# POWER.net
KiCad netlist of a schematic drawn in Altium Designer
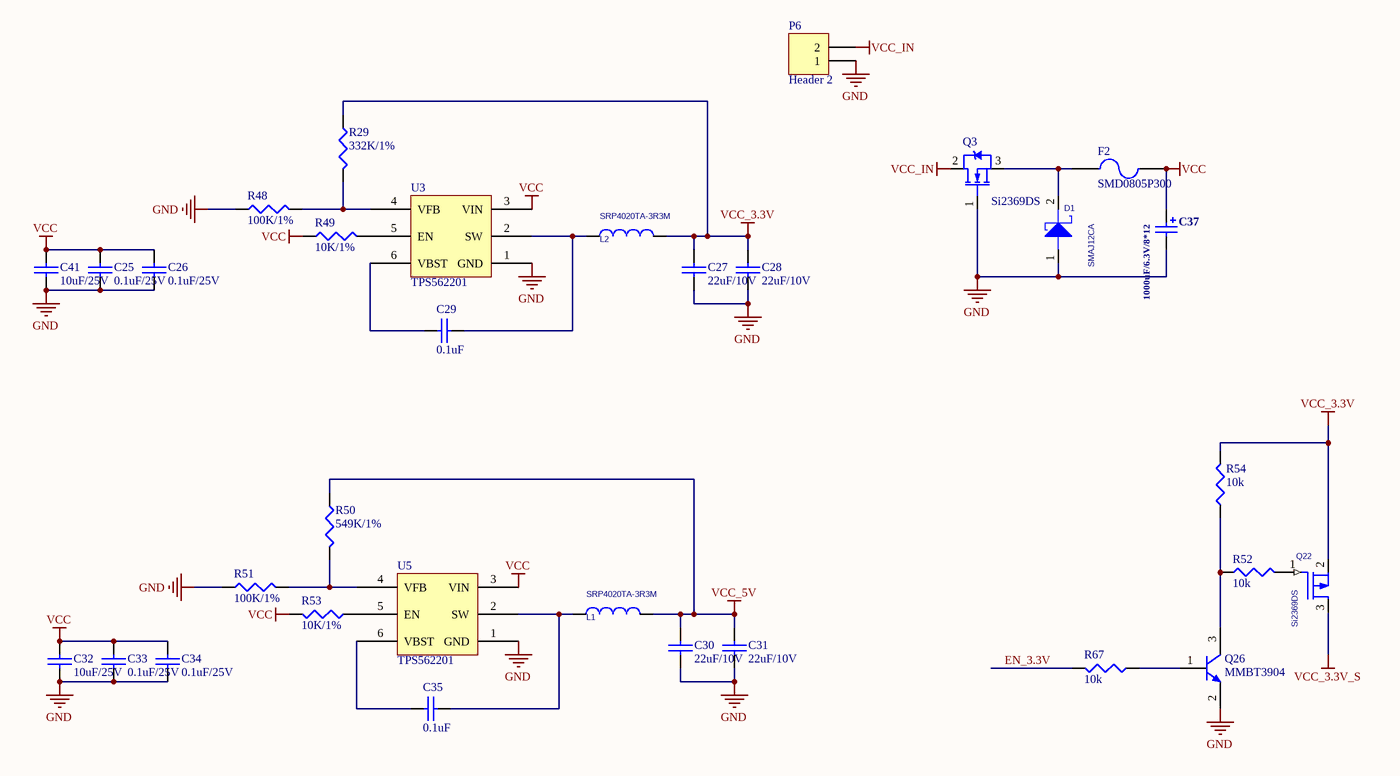
[diagram p0: POWER.SchDoc]

(export (version "E")
  (design (tool "Eeschema 10.0.6"))
  (components
    (comp (ref "C25")
      (value "0.1uF/25V")
      (footprint "0603C")
      (description "Capacitor")
      (libsource (lib "ZWLIntegrated_Library") (part "CAP"))
    )
    (comp (ref "C26")
      (value "0.1uF/25V")
      (footprint "0603C")
      (description "Capacitor")
      (libsource (lib "ZWLIntegrated_Library") (part "CAP"))
    )
    (comp (ref "C27")
      (value "22uF/10V")
      (footprint "1206C")
      (description "Capacitor")
      (libsource (lib "ZWLIntegrated_Library") (part "CAP"))
    )
    (comp (ref "C28")
      (value "22uF/10V")
      (footprint "1206C")
      (description "Capacitor")
      (libsource (lib "ZWLIntegrated_Library") (part "CAP"))
    )
    (comp (ref "C29")
      (value "0.1uF")
      (footprint "0603C")
      (description "Capacitor")
      (libsource (lib "ZWLIntegrated_Library") (part "CAP"))
    )
    (comp (ref "C30")
      (value "22uF/10V")
      (footprint "1206C")
      (description "Capacitor")
      (libsource (lib "ZWLIntegrated_Library") (part "CAP"))
    )
    (comp (ref "C31")
      (value "22uF/10V")
      (footprint "1206C")
      (description "Capacitor")
      (libsource (lib "ZWLIntegrated_Library") (part "CAP"))
    )
    (comp (ref "C32")
      (value "10uF/25V")
      (footprint "0603C")
      (description "Capacitor")
      (libsource (lib "ZWLIntegrated_Library") (part "CAP"))
    )
    (comp (ref "C33")
      (value "0.1uF/25V")
      (footprint "0603C")
      (description "Capacitor")
      (libsource (lib "ZWLIntegrated_Library") (part "CAP"))
    )
    (comp (ref "C34")
      (value "0.1uF/25V")
      (footprint "0603C")
      (description "Capacitor")
      (libsource (lib "ZWLIntegrated_Library") (part "CAP"))
    )
    (comp (ref "C35")
      (value "0.1uF")
      (footprint "0603C")
      (description "Capacitor")
      (libsource (lib "ZWLIntegrated_Library") (part "CAP"))
    )
    (comp (ref "C37")
      (value "1000uF/6.3V/8*12")
      (footprint "8*12")
      (description "Polarized Capacitor (Surface Mount)")
      (libsource (lib "KT_iBeacon") (part "Cap Pol3"))
    )
    (comp (ref "C41")
      (value "10uF/25V")
      (footprint "0603C")
      (description "Capacitor")
      (libsource (lib "ZWLIntegrated_Library") (part "CAP"))
    )
    (comp (ref "D1")
      (value "SMAJ12CA")
      (footprint "SMA")
      (libsource (lib "KT_iBeacon") (part "DIODE_SCHOTTKY_0"))
    )
    (comp (ref "F2")
      (value "SMD0805P300")
      (footprint "0805R")
      (description "Fuse")
      (fields (field (name "PUBLISHER") "Altium Limited"))
      (libsource (lib "Miscellaneous Devices") (part "Fuse 2"))
    )
    (comp (ref "L1") (value "SRP4020TA-3R3M") (footprint "CD_4*4") (libsource (lib "*") (part "INDUCTOR_1")))
    (comp (ref "L2") (value "SRP4020TA-3R3M") (footprint "CD_4*4") (libsource (lib "*") (part "INDUCTOR_1")))
    (comp (ref "P6")
      (value "Header 2")
      (footprint "2X2.54MMZ")
      (description "Header, 2-Pin")
      (fields (field (name "PUBLISHER") "Altium Limited"))
      (libsource (lib "Miscellaneous Connectors") (part "Header 2"))
    )
    (comp (ref "Q3")
      (value "Si2369DS")
      (footprint "sot23-3")
      (description "NMOSFET")
      (libsource (lib "SM") (part "NCE4060K"))
    )
    (comp (ref "Q22") (value "Si2369DS") (footprint "SOT23") (libsource (lib "*") (part "MOSFET P_1")))
    (comp (ref "Q26") (value "MMBT3904") (footprint "SOT23-3") (libsource (lib "Schlib1") (part "NPN")))
    (comp (ref "R29")
      (value "332K/1%")
      (footprint "0603R")
      (libsource (lib "ZWLIntegrated_Library") (part "RES1"))
    )
    (comp (ref "R48")
      (value "100K/1%")
      (footprint "0603R")
      (libsource (lib "ZWLIntegrated_Library") (part "RES1"))
    )
    (comp (ref "R49")
      (value "10K/1%")
      (footprint "0603R")
      (libsource (lib "ZWLIntegrated_Library") (part "RES1"))
    )
    (comp (ref "R50")
      (value "549K/1%")
      (footprint "0603R")
      (libsource (lib "ZWLIntegrated_Library") (part "RES1"))
    )
    (comp (ref "R51")
      (value "100K/1%")
      (footprint "0603R")
      (libsource (lib "ZWLIntegrated_Library") (part "RES1"))
    )
    (comp (ref "R52")
      (value "10k")
      (footprint "0603R")
      (libsource (lib "ZWLIntegrated_Library") (part "RES1"))
    )
    (comp (ref "R53")
      (value "10K/1%")
      (footprint "0603R")
      (libsource (lib "ZWLIntegrated_Library") (part "RES1"))
    )
    (comp (ref "R54")
      (value "10k")
      (footprint "0603R")
      (libsource (lib "ZWLIntegrated_Library") (part "RES1"))
    )
    (comp (ref "R67")
      (value "10k")
      (footprint "0603R")
      (libsource (lib "ZWLIntegrated_Library") (part "RES1"))
    )
    (comp (ref "U3")
      (value "TPS562201")
      (footprint "SOT-23-6")
      (libsource (lib "Schlib_20110825") (part "TPS562201"))
    )
    (comp (ref "U5")
      (value "TPS562201")
      (footprint "SOT-23-6")
      (libsource (lib "Schlib_20110825") (part "TPS562201"))
    )
  )
  (nets
    (net (code "1") (name "/EN_3.3V") (class "Default")
      (node (ref "R67") (pin "2") (pinfunction "2_2") (pintype "passive"))
    )
    (net (code "2") (name "GND") (class "Default")
      (node (ref "C25") (pin "1") (pinfunction "1_1") (pintype "passive"))
      (node (ref "C26") (pin "1") (pinfunction "1_1") (pintype "passive"))
      (node (ref "C27") (pin "2") (pinfunction "2_2") (pintype "passive"))
      (node (ref "C28") (pin "2") (pinfunction "2_2") (pintype "passive"))
      (node (ref "C30") (pin "2") (pinfunction "2_2") (pintype "passive"))
      (node (ref "C31") (pin "2") (pinfunction "2_2") (pintype "passive"))
      (node (ref "C32") (pin "1") (pinfunction "1_1") (pintype "passive"))
      (node (ref "C33") (pin "1") (pinfunction "1_1") (pintype "passive"))
      (node (ref "C34") (pin "1") (pinfunction "1_1") (pintype "passive"))
      (node (ref "C37") (pin "2") (pinfunction "2_2") (pintype "passive"))
      (node (ref "C41") (pin "1") (pinfunction "1_1") (pintype "passive"))
      (node (ref "D1") (pin "1") (pinfunction "1_1") (pintype "passive"))
      (node (ref "P6") (pin "1") (pinfunction "1_1") (pintype "passive"))
      (node (ref "Q26") (pin "2") (pinfunction "E_2") (pintype "passive"))
      (node (ref "Q3") (pin "1") (pinfunction "G_1") (pintype "passive"))
      (node (ref "R48") (pin "1") (pinfunction "1_1") (pintype "passive"))
      (node (ref "R51") (pin "1") (pinfunction "1_1") (pintype "passive"))
      (node (ref "U3") (pin "1") (pinfunction "GND_1") (pintype "passive"))
      (node (ref "U5") (pin "1") (pinfunction "GND_1") (pintype "passive"))
    )
    (net (code "3") (name "Net-(Q3-S)") (class "Default")
      (node (ref "D1") (pin "2") (pinfunction "2_2") (pintype "passive"))
      (node (ref "F2") (pin "1") (pinfunction "1_1") (pintype "passive"))
      (node (ref "Q3") (pin "3") (pinfunction "S_3") (pintype "passive"))
    )
    (net (code "4") (name "Net-(Q22-GATE)") (class "Default")
      (node (ref "Q22") (pin "1") (pinfunction "GATE_1") (pintype "input"))
      (node (ref "R52") (pin "2") (pinfunction "2_2") (pintype "passive"))
    )
    (net (code "5") (name "Net-(Q26-B)") (class "Default")
      (node (ref "Q26") (pin "1") (pinfunction "B_1") (pintype "passive"))
      (node (ref "R67") (pin "1") (pinfunction "1_1") (pintype "passive"))
    )
    (net (code "6") (name "Net-(Q26-C)") (class "Default")
      (node (ref "Q26") (pin "3") (pinfunction "C_3") (pintype "passive"))
      (node (ref "R52") (pin "1") (pinfunction "1_1") (pintype "passive"))
      (node (ref "R54") (pin "1") (pinfunction "1_1") (pintype "passive"))
    )
    (net (code "7") (name "Net-(U3-EN)") (class "Default")
      (node (ref "R49") (pin "2") (pinfunction "2_2") (pintype "passive"))
      (node (ref "U3") (pin "5") (pinfunction "EN_5") (pintype "passive"))
    )
    (net (code "8") (name "Net-(U3-SW)") (class "Default")
      (node (ref "C29") (pin "1") (pinfunction "1_1") (pintype "passive"))
      (node (ref "L2") (pin "1") (pinfunction "1_1") (pintype "passive"))
      (node (ref "U3") (pin "2") (pinfunction "SW_2") (pintype "passive"))
    )
    (net (code "9") (name "Net-(U3-VBST)") (class "Default")
      (node (ref "C29") (pin "2") (pinfunction "2_2") (pintype "passive"))
      (node (ref "U3") (pin "6") (pinfunction "VBST_6") (pintype "passive"))
    )
    (net (code "10") (name "Net-(U3-VFB)") (class "Default")
      (node (ref "R29") (pin "2") (pinfunction "2_2") (pintype "passive"))
      (node (ref "R48") (pin "2") (pinfunction "2_2") (pintype "passive"))
      (node (ref "U3") (pin "4") (pinfunction "VFB_4") (pintype "passive"))
    )
    (net (code "11") (name "Net-(U5-EN)") (class "Default")
      (node (ref "R53") (pin "1") (pinfunction "1_1") (pintype "passive"))
      (node (ref "U5") (pin "5") (pinfunction "EN_5") (pintype "passive"))
    )
    (net (code "12") (name "Net-(U5-SW)") (class "Default")
      (node (ref "C35") (pin "1") (pinfunction "1_1") (pintype "passive"))
      (node (ref "L1") (pin "1") (pinfunction "1_1") (pintype "passive"))
      (node (ref "U5") (pin "2") (pinfunction "SW_2") (pintype "passive"))
    )
    (net (code "13") (name "Net-(U5-VBST)") (class "Default")
      (node (ref "C35") (pin "2") (pinfunction "2_2") (pintype "passive"))
      (node (ref "U5") (pin "6") (pinfunction "VBST_6") (pintype "passive"))
    )
    (net (code "14") (name "Net-(U5-VFB)") (class "Default")
      (node (ref "R50") (pin "2") (pinfunction "2_2") (pintype "passive"))
      (node (ref "R51") (pin "2") (pinfunction "2_2") (pintype "passive"))
      (node (ref "U5") (pin "4") (pinfunction "VFB_4") (pintype "passive"))
    )
    (net (code "15") (name "VCC") (class "Default")
      (node (ref "C25") (pin "2") (pinfunction "2_2") (pintype "passive"))
      (node (ref "C26") (pin "2") (pinfunction "2_2") (pintype "passive"))
      (node (ref "C32") (pin "2") (pinfunction "2_2") (pintype "passive"))
      (node (ref "C33") (pin "2") (pinfunction "2_2") (pintype "passive"))
      (node (ref "C34") (pin "2") (pinfunction "2_2") (pintype "passive"))
      (node (ref "C37") (pin "1") (pinfunction "1_1") (pintype "passive"))
      (node (ref "C41") (pin "2") (pinfunction "2_2") (pintype "passive"))
      (node (ref "F2") (pin "2") (pinfunction "2_2") (pintype "passive"))
      (node (ref "R49") (pin "1") (pinfunction "1_1") (pintype "passive"))
      (node (ref "R53") (pin "2") (pinfunction "2_2") (pintype "passive"))
      (node (ref "U3") (pin "3") (pinfunction "VIN_3") (pintype "passive"))
      (node (ref "U5") (pin "3") (pinfunction "VIN_3") (pintype "passive"))
    )
    (net (code "16") (name "VCC_3.3V") (class "Default")
      (node (ref "C27") (pin "1") (pinfunction "1_1") (pintype "passive"))
      (node (ref "C28") (pin "1") (pinfunction "1_1") (pintype "passive"))
      (node (ref "L2") (pin "2") (pinfunction "2_2") (pintype "passive"))
      (node (ref "Q22") (pin "2") (pinfunction "DRAIN_2") (pintype "passive"))
      (node (ref "R29") (pin "1") (pinfunction "1_1") (pintype "passive"))
      (node (ref "R54") (pin "2") (pinfunction "2_2") (pintype "passive"))
    )
    (net (code "17") (name "VCC_3.3V_S") (class "Default")
      (node (ref "Q22") (pin "3") (pinfunction "SOURCE_3") (pintype "passive"))
    )
    (net (code "18") (name "VCC_5V") (class "Default")
      (node (ref "C30") (pin "1") (pinfunction "1_1") (pintype "passive"))
      (node (ref "C31") (pin "1") (pinfunction "1_1") (pintype "passive"))
      (node (ref "L1") (pin "2") (pinfunction "2_2") (pintype "passive"))
      (node (ref "R50") (pin "1") (pinfunction "1_1") (pintype "passive"))
    )
    (net (code "19") (name "VCC_IN") (class "Default")
      (node (ref "P6") (pin "2") (pinfunction "2_2") (pintype "passive"))
      (node (ref "Q3") (pin "2") (pinfunction "D_2") (pintype "passive"))
    )
  )
)
